# pov_display.net
KiCad netlist of a schematic drawn in EAGLE
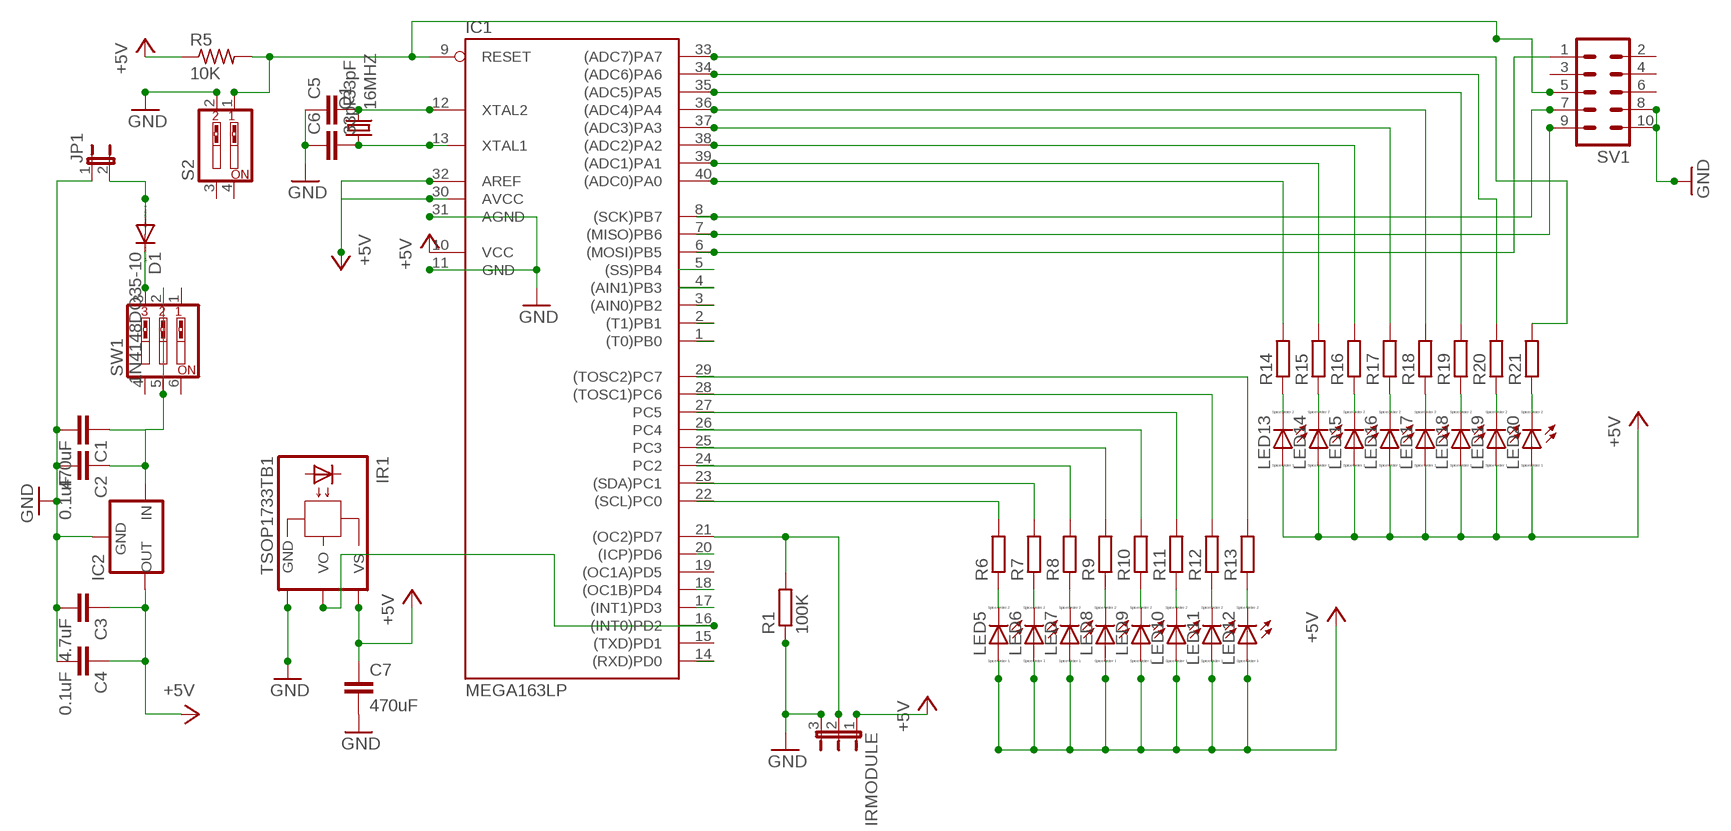
[diagram p0: schematic, sheet 1]

(export (version "E")
  (design (tool "Eeschema 10.0.6"))
  (components
    (comp (ref "C1")
      (value "470uF")
      (footprint "eagle-import:C2.5-4")
      (libsource (lib "eagle-import") (part "C2.5/4"))
    )
    (comp (ref "C2")
      (value "0.1uF")
      (footprint "eagle-import:C2.5-4")
      (libsource (lib "eagle-import") (part "C2.5/4"))
    )
    (comp (ref "C3")
      (value "4.7uF")
      (footprint "eagle-import:C2.5-4")
      (libsource (lib "eagle-import") (part "C2.5/4"))
    )
    (comp (ref "C4")
      (value "0.1uF")
      (footprint "eagle-import:C2.5-4")
      (libsource (lib "eagle-import") (part "C2.5/4"))
    )
    (comp (ref "C5")
      (value "33pF")
      (footprint "eagle-import:C2.5-4")
      (libsource (lib "eagle-import") (part "C2.5/4"))
    )
    (comp (ref "C6")
      (value "33pF")
      (footprint "eagle-import:C2.5-4")
      (libsource (lib "eagle-import") (part "C2.5/4"))
    )
    (comp (ref "C7")
      (value "470uF")
      (footprint "eagle-import:C2.5-4")
      (libsource (lib "eagle-import") (part "C2.5/4"))
    )
    (comp (ref "D1")
      (value "1N4148DO35-10")
      (footprint "eagle-import:DO35-10")
      (libsource (lib "eagle-import") (part "1N4148DO35-10"))
    )
    (comp (ref "IC1")
      (value "MEGA163LP")
      (footprint "eagle-import:DIL40")
      (libsource (lib "eagle-import") (part "MEGA163PL"))
    )
    (comp (ref "IC2")
      (value "78XXS")
      (footprint "eagle-import:78XXS")
      (libsource (lib "eagle-import") (part "78XXS"))
    )
    (comp (ref "IR1")
      (value "TSOP1733TB1")
      (footprint "eagle-import:TSOP17_TB1")
      (libsource (lib "eagle-import") (part "TSOP17TB133"))
    )
    (comp (ref "IRMODULE")
      (value "JP2W")
      (footprint "eagle-import:JP2W")
      (libsource (lib "eagle-import") (part "JP2W"))
    )
    (comp (ref "JP1")
      (value "JP1E")
      (footprint "eagle-import:JP1")
      (libsource (lib "eagle-import") (part "JP1E"))
    )
    (comp (ref "LED5")
      (value "LED_ELD260")
      (footprint "eagle-import:LED_LD260")
      (libsource (lib "eagle-import") (part "LED_ELD260"))
    )
    (comp (ref "LED6")
      (value "LED_ELD260")
      (footprint "eagle-import:LED_LD260")
      (libsource (lib "eagle-import") (part "LED_ELD260"))
    )
    (comp (ref "LED7")
      (value "LED_ELD260")
      (footprint "eagle-import:LED_LD260")
      (libsource (lib "eagle-import") (part "LED_ELD260"))
    )
    (comp (ref "LED8")
      (value "LED_ELD260")
      (footprint "eagle-import:LED_LD260")
      (libsource (lib "eagle-import") (part "LED_ELD260"))
    )
    (comp (ref "LED9")
      (value "LED_ELD260")
      (footprint "eagle-import:LED_LD260")
      (libsource (lib "eagle-import") (part "LED_ELD260"))
    )
    (comp (ref "LED10")
      (value "LED_ELD260")
      (footprint "eagle-import:LED_LD260")
      (libsource (lib "eagle-import") (part "LED_ELD260"))
    )
    (comp (ref "LED11")
      (value "LED_ELD260")
      (footprint "eagle-import:LED_LD260")
      (libsource (lib "eagle-import") (part "LED_ELD260"))
    )
    (comp (ref "LED12")
      (value "LED_ELD260")
      (footprint "eagle-import:LED_LD260")
      (libsource (lib "eagle-import") (part "LED_ELD260"))
    )
    (comp (ref "LED13")
      (value "LED_ELD260")
      (footprint "eagle-import:LED_LD260")
      (libsource (lib "eagle-import") (part "LED_ELD260"))
    )
    (comp (ref "LED14")
      (value "LED_ELD260")
      (footprint "eagle-import:LED_LD260")
      (libsource (lib "eagle-import") (part "LED_ELD260"))
    )
    (comp (ref "LED15")
      (value "LED_ELD260")
      (footprint "eagle-import:LED_LD260")
      (libsource (lib "eagle-import") (part "LED_ELD260"))
    )
    (comp (ref "LED16")
      (value "LED_ELD260")
      (footprint "eagle-import:LED_LD260")
      (libsource (lib "eagle-import") (part "LED_ELD260"))
    )
    (comp (ref "LED17")
      (value "LED_ELD260")
      (footprint "eagle-import:LED_LD260")
      (libsource (lib "eagle-import") (part "LED_ELD260"))
    )
    (comp (ref "LED18")
      (value "LED_ELD260")
      (footprint "eagle-import:LED_LD260")
      (libsource (lib "eagle-import") (part "LED_ELD260"))
    )
    (comp (ref "LED19")
      (value "LED_ELD260")
      (footprint "eagle-import:LED_LD260")
      (libsource (lib "eagle-import") (part "LED_ELD260"))
    )
    (comp (ref "LED20")
      (value "LED_ELD260")
      (footprint "eagle-import:LED_LD260")
      (libsource (lib "eagle-import") (part "LED_ELD260"))
    )
    (comp (ref "Q1")
      (value "16MHZ")
      (footprint "eagle-import:HC49U-V")
      (libsource (lib "eagle-import") (part "CRYSTALHC49U-V"))
    )
    (comp (ref "R1")
      (value "100K")
      (footprint "eagle-import:0207_7")
      (libsource (lib "eagle-import") (part "R-EU_0207/7"))
    )
    (comp (ref "R5")
      (value "10K")
      (footprint "eagle-import:0204_7")
      (libsource (lib "eagle-import") (part "R-US_0204/7"))
    )
    (comp (ref "R6")
      (value "R-EU_0207/7")
      (footprint "eagle-import:0207_7")
      (libsource (lib "eagle-import") (part "R-EU_0207/7"))
    )
    (comp (ref "R7")
      (value "R-EU_0207/7")
      (footprint "eagle-import:0207_7")
      (libsource (lib "eagle-import") (part "R-EU_0207/7"))
    )
    (comp (ref "R8")
      (value "R-EU_0207/7")
      (footprint "eagle-import:0207_7")
      (libsource (lib "eagle-import") (part "R-EU_0207/7"))
    )
    (comp (ref "R9")
      (value "R-EU_0207/7")
      (footprint "eagle-import:0207_7")
      (libsource (lib "eagle-import") (part "R-EU_0207/7"))
    )
    (comp (ref "R10")
      (value "R-EU_0207/7")
      (footprint "eagle-import:0207_7")
      (libsource (lib "eagle-import") (part "R-EU_0207/7"))
    )
    (comp (ref "R11")
      (value "R-EU_0207/7")
      (footprint "eagle-import:0207_7")
      (libsource (lib "eagle-import") (part "R-EU_0207/7"))
    )
    (comp (ref "R12")
      (value "R-EU_0207/7")
      (footprint "eagle-import:0207_7")
      (libsource (lib "eagle-import") (part "R-EU_0207/7"))
    )
    (comp (ref "R13")
      (value "R-EU_0207/7")
      (footprint "eagle-import:0207_7")
      (libsource (lib "eagle-import") (part "R-EU_0207/7"))
    )
    (comp (ref "R14")
      (value "R-EU_0207/7")
      (footprint "eagle-import:0207_7")
      (libsource (lib "eagle-import") (part "R-EU_0207/7"))
    )
    (comp (ref "R15")
      (value "R-EU_0207/7")
      (footprint "eagle-import:0207_7")
      (libsource (lib "eagle-import") (part "R-EU_0207/7"))
    )
    (comp (ref "R16")
      (value "R-EU_0207/7")
      (footprint "eagle-import:0207_7")
      (libsource (lib "eagle-import") (part "R-EU_0207/7"))
    )
    (comp (ref "R17")
      (value "R-EU_0207/7")
      (footprint "eagle-import:0207_7")
      (libsource (lib "eagle-import") (part "R-EU_0207/7"))
    )
    (comp (ref "R18")
      (value "R-EU_0207/7")
      (footprint "eagle-import:0207_7")
      (libsource (lib "eagle-import") (part "R-EU_0207/7"))
    )
    (comp (ref "R19")
      (value "R-EU_0207/7")
      (footprint "eagle-import:0207_7")
      (libsource (lib "eagle-import") (part "R-EU_0207/7"))
    )
    (comp (ref "R20")
      (value "R-EU_0207/7")
      (footprint "eagle-import:0207_7")
      (libsource (lib "eagle-import") (part "R-EU_0207/7"))
    )
    (comp (ref "R21")
      (value "R-EU_0207/7")
      (footprint "eagle-import:0207_7")
      (libsource (lib "eagle-import") (part "R-EU_0207/7"))
    )
    (comp (ref "S2")
      (value "SW_DIP-2")
      (footprint "eagle-import:EDG-02")
      (libsource (lib "eagle-import") (part "SW_DIP-2"))
    )
    (comp (ref "SV1")
      (value "MA05-2")
      (footprint "eagle-import:MA05-2")
      (libsource (lib "eagle-import") (part "MA05-2"))
    )
    (comp (ref "SW1")
      (value "SW_DIP-3")
      (footprint "eagle-import:EDG-03")
      (libsource (lib "eagle-import") (part "SW_DIP-3"))
    )
  )
  (nets
    (net (code "1") (name "+5V") (class "Default")
      (node (ref "C3") (pin "1") (pinfunction "1_1") (pintype "passive"))
      (node (ref "C4") (pin "1") (pinfunction "1_1") (pintype "passive"))
      (node (ref "C7") (pin "1") (pinfunction "1_1") (pintype "passive"))
      (node (ref "IC1") (pin "10") (pinfunction "VCC_10") (pintype "power_in"))
      (node (ref "IC1") (pin "30") (pinfunction "AVCC_30") (pintype "power_in"))
      (node (ref "IC1") (pin "32") (pinfunction "AREF_32") (pintype "passive"))
      (node (ref "IC2") (pin "OUT") (pinfunction "OUT_OUT") (pintype "passive"))
      (node (ref "IR1") (pin "VS") (pinfunction "VS_VS") (pintype "power_in"))
      (node (ref "IRMODULE") (pin "1") (pinfunction "1_1") (pintype "passive"))
      (node (ref "LED10") (pin "A") (pinfunction "A_A") (pintype "passive"))
      (node (ref "LED11") (pin "A") (pinfunction "A_A") (pintype "passive"))
      (node (ref "LED12") (pin "A") (pinfunction "A_A") (pintype "passive"))
      (node (ref "LED13") (pin "A") (pinfunction "A_A") (pintype "passive"))
      (node (ref "LED14") (pin "A") (pinfunction "A_A") (pintype "passive"))
      (node (ref "LED15") (pin "A") (pinfunction "A_A") (pintype "passive"))
      (node (ref "LED16") (pin "A") (pinfunction "A_A") (pintype "passive"))
      (node (ref "LED17") (pin "A") (pinfunction "A_A") (pintype "passive"))
      (node (ref "LED18") (pin "A") (pinfunction "A_A") (pintype "passive"))
      (node (ref "LED19") (pin "A") (pinfunction "A_A") (pintype "passive"))
      (node (ref "LED20") (pin "A") (pinfunction "A_A") (pintype "passive"))
      (node (ref "LED5") (pin "A") (pinfunction "A_A") (pintype "passive"))
      (node (ref "LED6") (pin "A") (pinfunction "A_A") (pintype "passive"))
      (node (ref "LED7") (pin "A") (pinfunction "A_A") (pintype "passive"))
      (node (ref "LED8") (pin "A") (pinfunction "A_A") (pintype "passive"))
      (node (ref "LED9") (pin "A") (pinfunction "A_A") (pintype "passive"))
      (node (ref "R5") (pin "1") (pinfunction "1_1") (pintype "passive"))
    )
    (net (code "2") (name "GND") (class "Default")
      (node (ref "C1") (pin "2") (pinfunction "2_2") (pintype "passive"))
      (node (ref "C2") (pin "2") (pinfunction "2_2") (pintype "passive"))
      (node (ref "C3") (pin "2") (pinfunction "2_2") (pintype "passive"))
      (node (ref "C4") (pin "2") (pinfunction "2_2") (pintype "passive"))
      (node (ref "C5") (pin "1") (pinfunction "1_1") (pintype "passive"))
      (node (ref "C6") (pin "1") (pinfunction "1_1") (pintype "passive"))
      (node (ref "C7") (pin "2") (pinfunction "2_2") (pintype "passive"))
      (node (ref "IC1") (pin "11") (pinfunction "GND_11") (pintype "power_in"))
      (node (ref "IC1") (pin "31") (pinfunction "AGND_31") (pintype "power_in"))
      (node (ref "IC2") (pin "GND") (pinfunction "GND_GND") (pintype "input"))
      (node (ref "IR1") (pin "GND") (pinfunction "GND_GND") (pintype "power_in"))
      (node (ref "IRMODULE") (pin "3") (pinfunction "3_3") (pintype "passive"))
      (node (ref "JP1") (pin "1") (pinfunction "1_1") (pintype "passive"))
      (node (ref "R1") (pin "1") (pinfunction "1_1") (pintype "passive"))
      (node (ref "S2") (pin "2") (pinfunction "2_2") (pintype "passive"))
      (node (ref "SV1") (pin "10") (pinfunction "10_10") (pintype "passive"))
      (node (ref "SV1") (pin "8") (pinfunction "8_8") (pintype "passive"))
    )
    (net (code "3") (name "Net-(C1-Pad1)") (class "Default")
      (node (ref "C1") (pin "1") (pinfunction "1_1") (pintype "passive"))
      (node (ref "C2") (pin "1") (pinfunction "1_1") (pintype "passive"))
      (node (ref "IC2") (pin "IN") (pinfunction "IN_IN") (pintype "input"))
      (node (ref "SW1") (pin "2") (pinfunction "2_2") (pintype "passive"))
      (node (ref "SW1") (pin "5") (pinfunction "5_5") (pintype "passive"))
    )
    (net (code "4") (name "Net-(D1-PadA)") (class "Default")
      (node (ref "D1") (pin "A") (pinfunction "A_A") (pintype "passive"))
      (node (ref "JP1") (pin "2") (pinfunction "2_2") (pintype "passive"))
    )
    (net (code "5") (name "Net-(D1-PadC)") (class "Default")
      (node (ref "D1") (pin "C") (pinfunction "C_C") (pintype "passive"))
      (node (ref "SW1") (pin "3") (pinfunction "3_3") (pintype "passive"))
    )
    (net (code "6") (name "Net-(IC1-(ADC0)PA0)") (class "Default")
      (node (ref "IC1") (pin "40") (pinfunction "(ADC0)PA0_40") (pintype "bidirectional"))
      (node (ref "R14") (pin "2") (pinfunction "2_2") (pintype "passive"))
    )
    (net (code "7") (name "Net-(IC1-(ADC1)PA1)") (class "Default")
      (node (ref "IC1") (pin "39") (pinfunction "(ADC1)PA1_39") (pintype "bidirectional"))
      (node (ref "R15") (pin "2") (pinfunction "2_2") (pintype "passive"))
    )
    (net (code "8") (name "Net-(IC1-(ADC2)PA2)") (class "Default")
      (node (ref "IC1") (pin "38") (pinfunction "(ADC2)PA2_38") (pintype "bidirectional"))
      (node (ref "R16") (pin "2") (pinfunction "2_2") (pintype "passive"))
    )
    (net (code "9") (name "Net-(IC1-(ADC3)PA3)") (class "Default")
      (node (ref "IC1") (pin "37") (pinfunction "(ADC3)PA3_37") (pintype "bidirectional"))
      (node (ref "R17") (pin "2") (pinfunction "2_2") (pintype "passive"))
    )
    (net (code "10") (name "Net-(IC1-(ADC4)PA4)") (class "Default")
      (node (ref "IC1") (pin "36") (pinfunction "(ADC4)PA4_36") (pintype "bidirectional"))
      (node (ref "R18") (pin "2") (pinfunction "2_2") (pintype "passive"))
    )
    (net (code "11") (name "Net-(IC1-(ADC5)PA5)") (class "Default")
      (node (ref "IC1") (pin "35") (pinfunction "(ADC5)PA5_35") (pintype "bidirectional"))
      (node (ref "R19") (pin "2") (pinfunction "2_2") (pintype "passive"))
    )
    (net (code "12") (name "Net-(IC1-(ADC6)PA6)") (class "Default")
      (node (ref "IC1") (pin "34") (pinfunction "(ADC6)PA6_34") (pintype "bidirectional"))
      (node (ref "R20") (pin "2") (pinfunction "2_2") (pintype "passive"))
    )
    (net (code "13") (name "Net-(IC1-(ADC7)PA7)") (class "Default")
      (node (ref "IC1") (pin "33") (pinfunction "(ADC7)PA7_33") (pintype "bidirectional"))
      (node (ref "R21") (pin "2") (pinfunction "2_2") (pintype "passive"))
    )
    (net (code "14") (name "Net-(IC1-(INT0)PD2)") (class "Default")
      (node (ref "IC1") (pin "16") (pinfunction "(INT0)PD2_16") (pintype "bidirectional"))
      (node (ref "IR1") (pin "VO") (pinfunction "VO_VO") (pintype "open_collector"))
    )
    (net (code "15") (name "Net-(IC1-(MISO)PB6)") (class "Default")
      (node (ref "IC1") (pin "7") (pinfunction "(MISO)PB6_7") (pintype "bidirectional"))
      (node (ref "SV1") (pin "9") (pinfunction "9_9") (pintype "passive"))
    )
    (net (code "16") (name "Net-(IC1-(MOSI)PB5)") (class "Default")
      (node (ref "IC1") (pin "6") (pinfunction "(MOSI)PB5_6") (pintype "bidirectional"))
      (node (ref "SV1") (pin "1") (pinfunction "1_1") (pintype "passive"))
    )
    (net (code "17") (name "Net-(IC1-(OC2)PD7)") (class "Default")
      (node (ref "IC1") (pin "21") (pinfunction "(OC2)PD7_21") (pintype "bidirectional"))
      (node (ref "IRMODULE") (pin "2") (pinfunction "2_2") (pintype "passive"))
      (node (ref "R1") (pin "2") (pinfunction "2_2") (pintype "passive"))
    )
    (net (code "18") (name "Net-(IC1-(SCK)PB7)") (class "Default")
      (node (ref "IC1") (pin "8") (pinfunction "(SCK)PB7_8") (pintype "bidirectional"))
      (node (ref "SV1") (pin "7") (pinfunction "7_7") (pintype "passive"))
    )
    (net (code "19") (name "Net-(IC1-(SCL)PC0)") (class "Default")
      (node (ref "IC1") (pin "22") (pinfunction "(SCL)PC0_22") (pintype "bidirectional"))
      (node (ref "R6") (pin "2") (pinfunction "2_2") (pintype "passive"))
    )
    (net (code "20") (name "Net-(IC1-(SDA)PC1)") (class "Default")
      (node (ref "IC1") (pin "23") (pinfunction "(SDA)PC1_23") (pintype "bidirectional"))
      (node (ref "R7") (pin "2") (pinfunction "2_2") (pintype "passive"))
    )
    (net (code "21") (name "Net-(IC1-(TOSC1)PC6)") (class "Default")
      (node (ref "IC1") (pin "28") (pinfunction "(TOSC1)PC6_28") (pintype "bidirectional"))
      (node (ref "R12") (pin "2") (pinfunction "2_2") (pintype "passive"))
    )
    (net (code "22") (name "Net-(IC1-(TOSC2)PC7)") (class "Default")
      (node (ref "IC1") (pin "29") (pinfunction "(TOSC2)PC7_29") (pintype "bidirectional"))
      (node (ref "R13") (pin "2") (pinfunction "2_2") (pintype "passive"))
    )
    (net (code "23") (name "Net-(IC1-PC2)") (class "Default")
      (node (ref "IC1") (pin "24") (pinfunction "PC2_24") (pintype "bidirectional"))
      (node (ref "R8") (pin "2") (pinfunction "2_2") (pintype "passive"))
    )
    (net (code "24") (name "Net-(IC1-PC3)") (class "Default")
      (node (ref "IC1") (pin "25") (pinfunction "PC3_25") (pintype "bidirectional"))
      (node (ref "R9") (pin "2") (pinfunction "2_2") (pintype "passive"))
    )
    (net (code "25") (name "Net-(IC1-PC4)") (class "Default")
      (node (ref "IC1") (pin "26") (pinfunction "PC4_26") (pintype "bidirectional"))
      (node (ref "R10") (pin "2") (pinfunction "2_2") (pintype "passive"))
    )
    (net (code "26") (name "Net-(IC1-PC5)") (class "Default")
      (node (ref "IC1") (pin "27") (pinfunction "PC5_27") (pintype "bidirectional"))
      (node (ref "R11") (pin "2") (pinfunction "2_2") (pintype "passive"))
    )
    (net (code "27") (name "Net-(IC1-RESET)") (class "Default")
      (node (ref "IC1") (pin "9") (pinfunction "RESET_9") (pintype "input"))
      (node (ref "R5") (pin "2") (pinfunction "2_2") (pintype "passive"))
      (node (ref "S2") (pin "1") (pinfunction "1_1") (pintype "passive"))
      (node (ref "SV1") (pin "5") (pinfunction "5_5") (pintype "passive"))
    )
    (net (code "28") (name "Net-(IC1-XTAL1)") (class "Default")
      (node (ref "C6") (pin "2") (pinfunction "2_2") (pintype "passive"))
      (node (ref "IC1") (pin "13") (pinfunction "XTAL1_13") (pintype "bidirectional"))
      (node (ref "Q1") (pin "1") (pinfunction "1_1") (pintype "passive"))
    )
    (net (code "29") (name "Net-(IC1-XTAL2)") (class "Default")
      (node (ref "C5") (pin "2") (pinfunction "2_2") (pintype "passive"))
      (node (ref "IC1") (pin "12") (pinfunction "XTAL2_12") (pintype "bidirectional"))
      (node (ref "Q1") (pin "2") (pinfunction "2_2") (pintype "passive"))
    )
    (net (code "30") (name "Net-(LED5-C)") (class "Default")
      (node (ref "LED5") (pin "K") (pinfunction "C_K") (pintype "passive"))
      (node (ref "R6") (pin "1") (pinfunction "1_1") (pintype "passive"))
    )
    (net (code "31") (name "Net-(LED6-C)") (class "Default")
      (node (ref "LED6") (pin "K") (pinfunction "C_K") (pintype "passive"))
      (node (ref "R7") (pin "1") (pinfunction "1_1") (pintype "passive"))
    )
    (net (code "32") (name "Net-(LED7-C)") (class "Default")
      (node (ref "LED7") (pin "K") (pinfunction "C_K") (pintype "passive"))
      (node (ref "R8") (pin "1") (pinfunction "1_1") (pintype "passive"))
    )
    (net (code "33") (name "Net-(LED8-C)") (class "Default")
      (node (ref "LED8") (pin "K") (pinfunction "C_K") (pintype "passive"))
      (node (ref "R9") (pin "1") (pinfunction "1_1") (pintype "passive"))
    )
    (net (code "34") (name "Net-(LED9-C)") (class "Default")
      (node (ref "LED9") (pin "K") (pinfunction "C_K") (pintype "passive"))
      (node (ref "R10") (pin "1") (pinfunction "1_1") (pintype "passive"))
    )
    (net (code "35") (name "Net-(LED10-C)") (class "Default")
      (node (ref "LED10") (pin "K") (pinfunction "C_K") (pintype "passive"))
      (node (ref "R11") (pin "1") (pinfunction "1_1") (pintype "passive"))
    )
    (net (code "36") (name "Net-(LED11-C)") (class "Default")
      (node (ref "LED11") (pin "K") (pinfunction "C_K") (pintype "passive"))
      (node (ref "R12") (pin "1") (pinfunction "1_1") (pintype "passive"))
    )
    (net (code "37") (name "Net-(LED12-C)") (class "Default")
      (node (ref "LED12") (pin "K") (pinfunction "C_K") (pintype "passive"))
      (node (ref "R13") (pin "1") (pinfunction "1_1") (pintype "passive"))
    )
    (net (code "38") (name "Net-(LED13-C)") (class "Default")
      (node (ref "LED13") (pin "K") (pinfunction "C_K") (pintype "passive"))
      (node (ref "R14") (pin "1") (pinfunction "1_1") (pintype "passive"))
    )
    (net (code "39") (name "Net-(LED14-C)") (class "Default")
      (node (ref "LED14") (pin "K") (pinfunction "C_K") (pintype "passive"))
      (node (ref "R15") (pin "1") (pinfunction "1_1") (pintype "passive"))
    )
    (net (code "40") (name "Net-(LED15-C)") (class "Default")
      (node (ref "LED15") (pin "K") (pinfunction "C_K") (pintype "passive"))
      (node (ref "R16") (pin "1") (pinfunction "1_1") (pintype "passive"))
    )
    (net (code "41") (name "Net-(LED16-C)") (class "Default")
      (node (ref "LED16") (pin "K") (pinfunction "C_K") (pintype "passive"))
      (node (ref "R17") (pin "1") (pinfunction "1_1") (pintype "passive"))
    )
    (net (code "42") (name "Net-(LED17-C)") (class "Default")
      (node (ref "LED17") (pin "K") (pinfunction "C_K") (pintype "passive"))
      (node (ref "R18") (pin "1") (pinfunction "1_1") (pintype "passive"))
    )
    (net (code "43") (name "Net-(LED18-C)") (class "Default")
      (node (ref "LED18") (pin "K") (pinfunction "C_K") (pintype "passive"))
      (node (ref "R19") (pin "1") (pinfunction "1_1") (pintype "passive"))
    )
    (net (code "44") (name "Net-(LED19-C)") (class "Default")
      (node (ref "LED19") (pin "K") (pinfunction "C_K") (pintype "passive"))
      (node (ref "R20") (pin "1") (pinfunction "1_1") (pintype "passive"))
    )
    (net (code "45") (name "Net-(LED20-C)") (class "Default")
      (node (ref "LED20") (pin "K") (pinfunction "C_K") (pintype "passive"))
      (node (ref "R21") (pin "1") (pinfunction "1_1") (pintype "passive"))
    )
    (net (code "46") (name "unconnected-(IC1-(AIN0)PB2-Pad3)") (class "Default")
      (node (ref "IC1") (pin "3") (pinfunction "(AIN0)PB2_3") (pintype "bidirectional"))
    )
    (net (code "47") (name "unconnected-(IC1-(AIN1)PB3-Pad4)") (class "Default")
      (node (ref "IC1") (pin "4") (pinfunction "(AIN1)PB3_4") (pintype "bidirectional"))
    )
    (net (code "48") (name "unconnected-(IC1-(ICP)PD6-Pad20)") (class "Default")
      (node (ref "IC1") (pin "20") (pinfunction "(ICP)PD6_20") (pintype "bidirectional"))
    )
    (net (code "49") (name "unconnected-(IC1-(INT1)PD3-Pad17)") (class "Default")
      (node (ref "IC1") (pin "17") (pinfunction "(INT1)PD3_17") (pintype "bidirectional"))
    )
    (net (code "50") (name "unconnected-(IC1-(OC1A)PD5-Pad19)") (class "Default")
      (node (ref "IC1") (pin "19") (pinfunction "(OC1A)PD5_19") (pintype "bidirectional"))
    )
    (net (code "51") (name "unconnected-(IC1-(OC1B)PD4-Pad18)") (class "Default")
      (node (ref "IC1") (pin "18") (pinfunction "(OC1B)PD4_18") (pintype "bidirectional"))
    )
    (net (code "52") (name "unconnected-(IC1-(RXD)PD0-Pad14)") (class "Default")
      (node (ref "IC1") (pin "14") (pinfunction "(RXD)PD0_14") (pintype "bidirectional"))
    )
    (net (code "53") (name "unconnected-(IC1-(SS)PB4-Pad5)") (class "Default")
      (node (ref "IC1") (pin "5") (pinfunction "(SS)PB4_5") (pintype "bidirectional"))
    )
    (net (code "54") (name "unconnected-(IC1-(T0)PB0-Pad1)") (class "Default")
      (node (ref "IC1") (pin "1") (pinfunction "(T0)PB0_1") (pintype "bidirectional"))
    )
    (net (code "55") (name "unconnected-(IC1-(T1)PB1-Pad2)") (class "Default")
      (node (ref "IC1") (pin "2") (pinfunction "(T1)PB1_2") (pintype "bidirectional"))
    )
    (net (code "56") (name "unconnected-(IC1-(TXD)PD1-Pad15)") (class "Default")
      (node (ref "IC1") (pin "15") (pinfunction "(TXD)PD1_15") (pintype "bidirectional"))
    )
    (net (code "57") (name "unconnected-(S2-Pad3)") (class "Default")
      (node (ref "S2") (pin "3") (pinfunction "3_3") (pintype "passive"))
    )
    (net (code "58") (name "unconnected-(S2-Pad4)") (class "Default")
      (node (ref "S2") (pin "4") (pinfunction "4_4") (pintype "passive"))
    )
    (net (code "59") (name "unconnected-(SV1-Pad2)") (class "Default")
      (node (ref "SV1") (pin "2") (pinfunction "2_2") (pintype "passive"))
    )
    (net (code "60") (name "unconnected-(SV1-Pad3)") (class "Default")
      (node (ref "SV1") (pin "3") (pinfunction "3_3") (pintype "passive"))
    )
    (net (code "61") (name "unconnected-(SV1-Pad4)") (class "Default")
      (node (ref "SV1") (pin "4") (pinfunction "4_4") (pintype "passive"))
    )
    (net (code "62") (name "unconnected-(SV1-Pad6)") (class "Default")
      (node (ref "SV1") (pin "6") (pinfunction "6_6") (pintype "passive"))
    )
    (net (code "63") (name "unconnected-(SW1-Pad1)") (class "Default")
      (node (ref "SW1") (pin "1") (pinfunction "1_1") (pintype "passive"))
    )
    (net (code "64") (name "unconnected-(SW1-Pad4)") (class "Default")
      (node (ref "SW1") (pin "4") (pinfunction "4_4") (pintype "passive"))
    )
    (net (code "65") (name "unconnected-(SW1-Pad6)") (class "Default")
      (node (ref "SW1") (pin "6") (pinfunction "6_6") (pintype "passive"))
    )
  )
)
